# Bank.net
KiCad netlist of a schematic drawn in Altium Designer
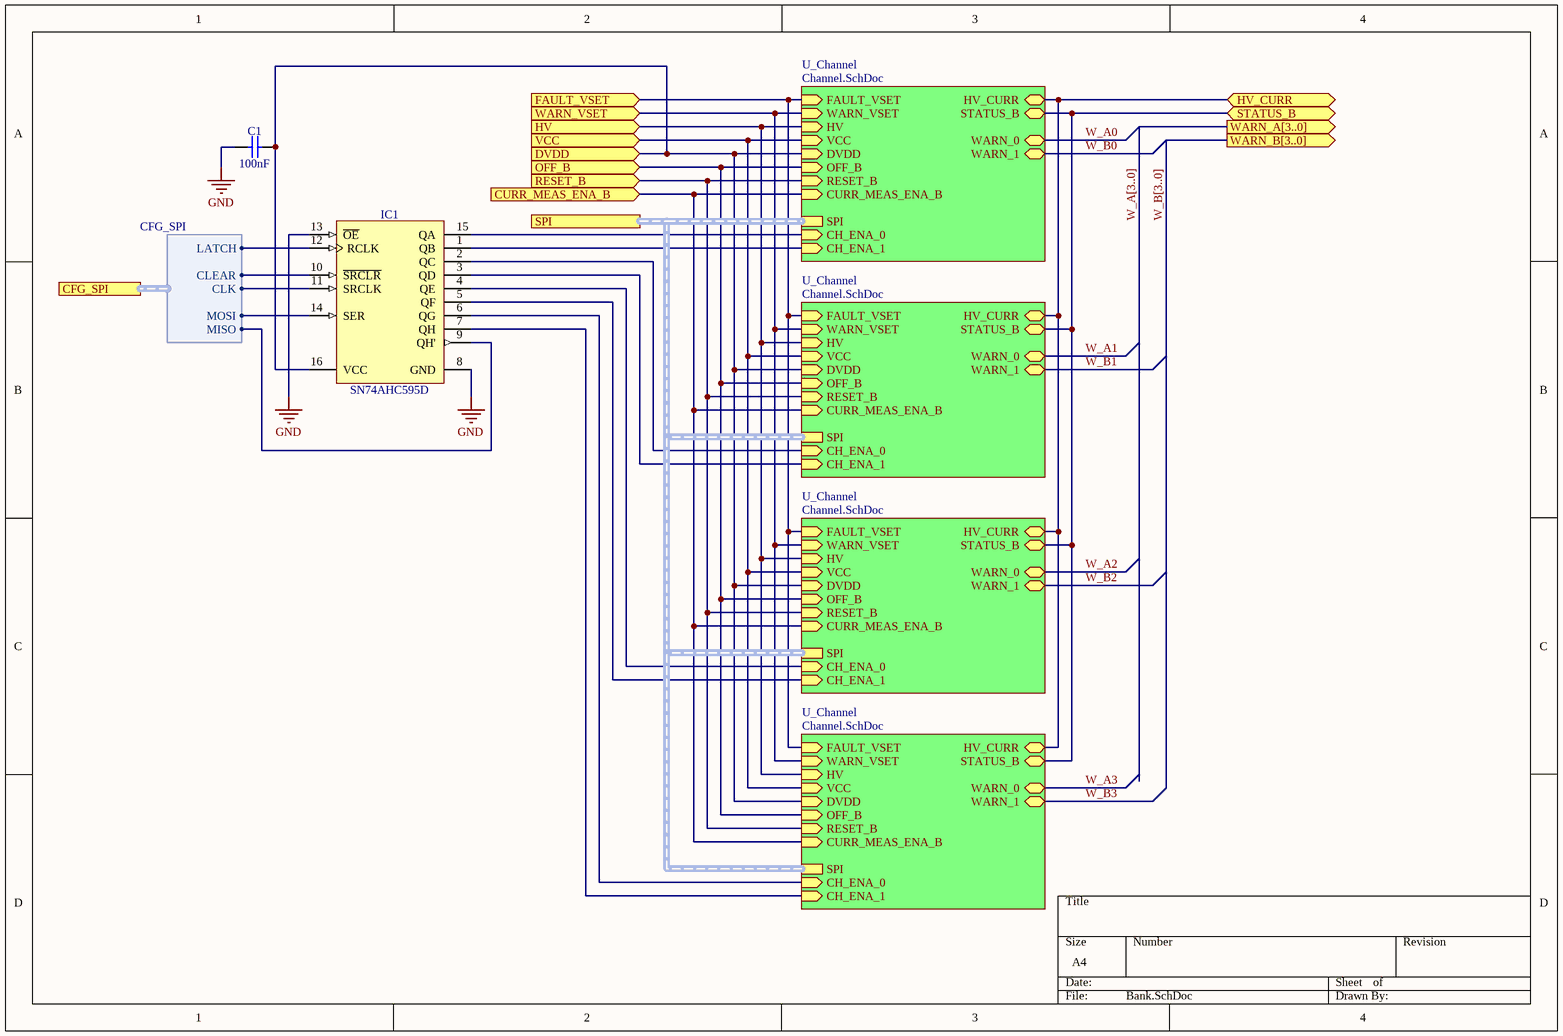
[diagram p0: Bank.SchDoc]

(export (version "E")
  (design (tool "Eeschema 10.0.6"))
  (components
    (comp (ref "C1")
      (value "100nF")
      (footprint "CAPC2012X135N")
      (description "Non-polarised capacitor")
      (fields
        (field (name "PART NUMBER") "CC0805_100NF_50V_10%_X7R")
        (field (name "VOLTAGE") "50V")
        (field (name "AUTHOR") "CERN DEM JLC")
      )
      (libsource (lib "Capacitors") (part "Capacitor - non polarized"))
    )
    (comp (ref "IC1")
      (value "SN74AHC595D")
      (footprint "SOIC127P600X175-16N")
      (description "8-Bit Shift Register With 3-State Output Register")
      (fields (field (name "MANUFACTURER") "TEXAS INSTRUMENTS") (field (name "AUTHOR") "CERN DEM JLC"))
      (libsource (lib "ICs And Semiconductors") (part "74595"))
    )
  )
  (nets
    (net (code "3") (name "/CH_ENA_0") (class "Default")
      (node (ref "IC1") (pin "6") (pinfunction "QG_6") (pintype "tri_state"))
    )
    (net (code "4") (name "/CH_ENA_0_1") (class "Default")
      (node (ref "IC1") (pin "2") (pinfunction "QC_2") (pintype "tri_state"))
    )
    (net (code "5") (name "/CH_ENA_0_2") (class "Default")
      (node (ref "IC1") (pin "15") (pinfunction "QA_15") (pintype "tri_state"))
    )
    (net (code "6") (name "/CH_ENA_0_3") (class "Default")
      (node (ref "IC1") (pin "4") (pinfunction "QE_4") (pintype "tri_state"))
    )
    (net (code "7") (name "/CH_ENA_1") (class "Default")
      (node (ref "IC1") (pin "7") (pinfunction "QH_7") (pintype "tri_state"))
    )
    (net (code "8") (name "/CH_ENA_1_1") (class "Default")
      (node (ref "IC1") (pin "3") (pinfunction "QD_3") (pintype "tri_state"))
    )
    (net (code "9") (name "/CH_ENA_1_2") (class "Default")
      (node (ref "IC1") (pin "1") (pinfunction "QB_1") (pintype "tri_state"))
    )
    (net (code "10") (name "/CH_ENA_1_3") (class "Default")
      (node (ref "IC1") (pin "5") (pinfunction "QF_5") (pintype "tri_state"))
    )
    (net (code "12") (name "/DVDD") (class "Default")
      (node (ref "C1") (pin "2") (pinfunction "2_2") (pintype "passive"))
      (node (ref "IC1") (pin "16") (pinfunction "VCC_16") (pintype "power_in"))
    )
    (net (code "33") (name "GND") (class "Default")
      (node (ref "C1") (pin "1") (pinfunction "1_1") (pintype "passive"))
      (node (ref "IC1") (pin "13") (pinfunction "~{OE}_13") (pintype "input"))
      (node (ref "IC1") (pin "8") (pinfunction "GND_8") (pintype "power_in"))
    )
    (net (code "34") (name "unconnected-(IC1-QH'-Pad9)") (class "Default")
      (node (ref "IC1") (pin "9") (pinfunction "QH'_9") (pintype "output"))
    )
    (net (code "35") (name "unconnected-(IC1-RCLK-Pad12)") (class "Default")
      (node (ref "IC1") (pin "12") (pinfunction "RCLK_12") (pintype "input"))
    )
    (net (code "36") (name "unconnected-(IC1-SER-Pad14)") (class "Default")
      (node (ref "IC1") (pin "14") (pinfunction "SER_14") (pintype "input"))
    )
    (net (code "37") (name "unconnected-(IC1-SRCLK-Pad11)") (class "Default")
      (node (ref "IC1") (pin "11") (pinfunction "SRCLK_11") (pintype "input"))
    )
    (net (code "38") (name "unconnected-(IC1-~{SRCLR}-Pad10)") (class "Default")
      (node (ref "IC1") (pin "10") (pinfunction "~{SRCLR}_10") (pintype "input"))
    )
  )
)
